# gpio_expander.net
KiCad netlist of a schematic drawn in Altium Designer
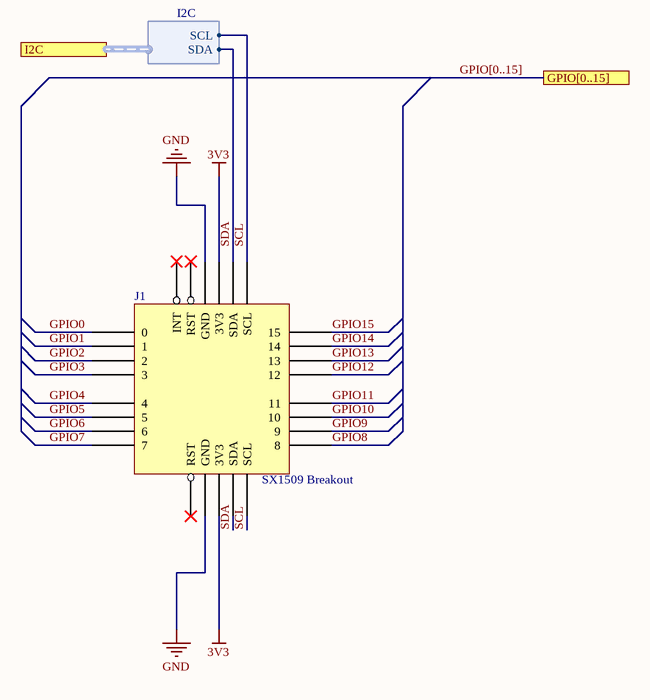
[diagram p0: gpio_expander.SchDoc]

(export (version "E")
  (design (tool "Eeschema 10.0.6"))
  (components
    (comp (ref "J1")
      (value "SX1509 Breakout")
      (footprint "SX1509 Breakout")
      (libsource (lib "brew_lib") (part "SX1509 Breakout"))
    )
  )
  (nets
    (net (code "2") (name "/GPIO0") (class "Default")
      (node (ref "J1") (pin "1") (pinfunction "0_1") (pintype "passive"))
    )
    (net (code "3") (name "/GPIO1") (class "Default")
      (node (ref "J1") (pin "2") (pinfunction "1_2") (pintype "passive"))
    )
    (net (code "4") (name "/GPIO2") (class "Default")
      (node (ref "J1") (pin "3") (pinfunction "2_3") (pintype "passive"))
    )
    (net (code "5") (name "/GPIO3") (class "Default")
      (node (ref "J1") (pin "4") (pinfunction "3_4") (pintype "passive"))
    )
    (net (code "6") (name "/GPIO4") (class "Default")
      (node (ref "J1") (pin "5") (pinfunction "4_5") (pintype "passive"))
    )
    (net (code "7") (name "/GPIO5") (class "Default")
      (node (ref "J1") (pin "6") (pinfunction "5_6") (pintype "passive"))
    )
    (net (code "8") (name "/GPIO6") (class "Default")
      (node (ref "J1") (pin "7") (pinfunction "6_7") (pintype "passive"))
    )
    (net (code "9") (name "/GPIO7") (class "Default")
      (node (ref "J1") (pin "8") (pinfunction "7_8") (pintype "passive"))
    )
    (net (code "10") (name "/GPIO8") (class "Default")
      (node (ref "J1") (pin "14") (pinfunction "8_14") (pintype "passive"))
    )
    (net (code "11") (name "/GPIO9") (class "Default")
      (node (ref "J1") (pin "15") (pinfunction "9_15") (pintype "passive"))
    )
    (net (code "12") (name "/GPIO10") (class "Default")
      (node (ref "J1") (pin "16") (pinfunction "10_16") (pintype "passive"))
    )
    (net (code "13") (name "/GPIO11") (class "Default")
      (node (ref "J1") (pin "17") (pinfunction "11_17") (pintype "passive"))
    )
    (net (code "14") (name "/GPIO12") (class "Default")
      (node (ref "J1") (pin "18") (pinfunction "12_18") (pintype "passive"))
    )
    (net (code "15") (name "/GPIO13") (class "Default")
      (node (ref "J1") (pin "19") (pinfunction "13_19") (pintype "passive"))
    )
    (net (code "16") (name "/GPIO14") (class "Default")
      (node (ref "J1") (pin "20") (pinfunction "14_20") (pintype "passive"))
    )
    (net (code "17") (name "/GPIO15") (class "Default")
      (node (ref "J1") (pin "21") (pinfunction "15_21") (pintype "passive"))
    )
    (net (code "19") (name "/SCL") (class "Default")
      (node (ref "J1") (pin "13") (pinfunction "SCL_13") (pintype "passive"))
      (node (ref "J1") (pin "22") (pinfunction "SCL_22") (pintype "passive"))
    )
    (net (code "20") (name "/SDA") (class "Default")
      (node (ref "J1") (pin "12") (pinfunction "SDA_12") (pintype "passive"))
      (node (ref "J1") (pin "23") (pinfunction "SDA_23") (pintype "passive"))
    )
    (net (code "22") (name "3V3") (class "Default")
      (node (ref "J1") (pin "11") (pinfunction "3V3_11") (pintype "passive"))
      (node (ref "J1") (pin "24") (pinfunction "3V3_24") (pintype "passive"))
    )
    (net (code "23") (name "GND") (class "Default")
      (node (ref "J1") (pin "10") (pinfunction "GND_10") (pintype "passive"))
      (node (ref "J1") (pin "25") (pinfunction "GND_25") (pintype "passive"))
    )
    (net (code "24") (name "unconnected-(J1-INT-Pad27)") (class "Default")
      (node (ref "J1") (pin "27") (pinfunction "INT_27") (pintype "passive+no_connect"))
    )
    (net (code "25") (name "unconnected-(J1-RST-Pad9)") (class "Default")
      (node (ref "J1") (pin "9") (pinfunction "RST_9") (pintype "passive+no_connect"))
    )
    (net (code "26") (name "unconnected-(J1-RST-Pad26)") (class "Default")
      (node (ref "J1") (pin "26") (pinfunction "RST_26") (pintype "passive+no_connect"))
    )
  )
)
